# fpga.net
KiCad netlist of a schematic drawn in Altium Designer
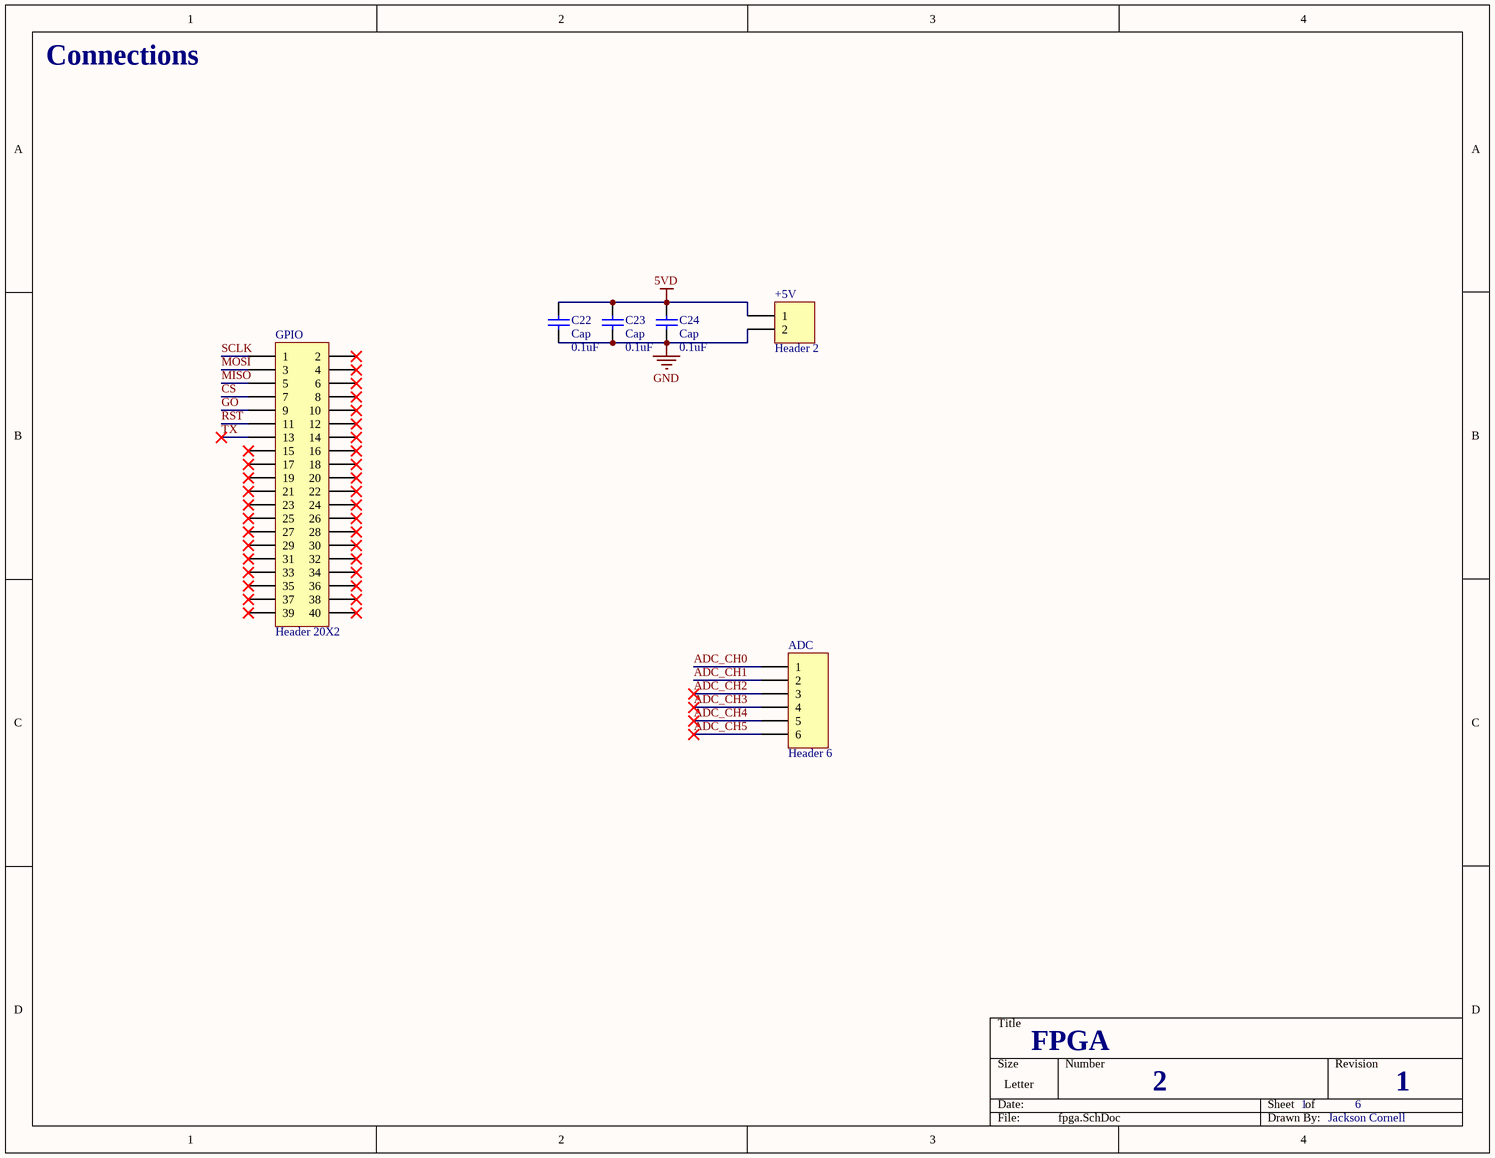
[diagram p0: fpga.SchDoc]

(export (version "E")
  (design (tool "Eeschema 10.0.6"))
  (components
    (comp (ref "+5V")
      (value "Header 2")
      (footprint "HDR1X2")
      (description "Header, 2-Pin")
      (fields (field (name "PUBLISHER") "Altium Limited"))
      (libsource (lib "Miscellaneous Connectors") (part "Header 2"))
    )
    (comp (ref "ADC")
      (value "Header 6")
      (footprint "HDR1X6")
      (description "Header, 6-Pin")
      (fields (field (name "PUBLISHER") "Altium Limited"))
      (libsource (lib "Miscellaneous Connectors") (part "Header 6"))
    )
    (comp (ref "C22")
      (value "Cap")
      (footprint "CAPC0805")
      (description "Capacitor")
      (fields (field (name "ALTIUM_VALUE") "0.1uF") (field (name "PUBLISHER") "Altium Limited"))
      (libsource (lib "Miscellaneous Devices") (part "Cap"))
    )
    (comp (ref "C23")
      (value "Cap")
      (footprint "CAPC0805")
      (description "Capacitor")
      (fields (field (name "ALTIUM_VALUE") "0.1uF") (field (name "PUBLISHER") "Altium Limited"))
      (libsource (lib "Miscellaneous Devices") (part "Cap"))
    )
    (comp (ref "C24")
      (value "Cap")
      (footprint "CAPC0805")
      (description "Capacitor")
      (fields (field (name "ALTIUM_VALUE") "0.1uF") (field (name "PUBLISHER") "Altium Limited"))
      (libsource (lib "Miscellaneous Devices") (part "Cap"))
    )
    (comp (ref "GPIO")
      (value "Header 20X2")
      (footprint "HDR2X20")
      (description "Header, 20-Pin, Dual row")
      (fields (field (name "PUBLISHER") "Altium Limited"))
      (libsource (lib "Miscellaneous Connectors") (part "Header 20X2"))
    )
  )
  (nets
    (net (code "1") (name "/ADC_CH0") (class "Default")
      (node (ref "ADC") (pin "1") (pinfunction "1_1") (pintype "passive"))
    )
    (net (code "2") (name "/ADC_CH1") (class "Default")
      (node (ref "ADC") (pin "2") (pinfunction "2_2") (pintype "passive"))
    )
    (net (code "3") (name "/ADC_CH2") (class "Default")
      (node (ref "ADC") (pin "3") (pinfunction "3_3") (pintype "passive+no_connect"))
    )
    (net (code "4") (name "/ADC_CH3") (class "Default")
      (node (ref "ADC") (pin "4") (pinfunction "4_4") (pintype "passive+no_connect"))
    )
    (net (code "5") (name "/ADC_CH4") (class "Default")
      (node (ref "ADC") (pin "5") (pinfunction "5_5") (pintype "passive+no_connect"))
    )
    (net (code "6") (name "/ADC_CH5") (class "Default")
      (node (ref "ADC") (pin "6") (pinfunction "6_6") (pintype "passive+no_connect"))
    )
    (net (code "7") (name "/CS") (class "Default")
      (node (ref "GPIO") (pin "7") (pinfunction "7_7") (pintype "passive"))
    )
    (net (code "8") (name "/GO") (class "Default")
      (node (ref "GPIO") (pin "9") (pinfunction "9_9") (pintype "passive"))
    )
    (net (code "9") (name "/MISO") (class "Default")
      (node (ref "GPIO") (pin "5") (pinfunction "5_5") (pintype "passive"))
    )
    (net (code "10") (name "/MOSI") (class "Default")
      (node (ref "GPIO") (pin "3") (pinfunction "3_3") (pintype "passive"))
    )
    (net (code "11") (name "/RST") (class "Default")
      (node (ref "GPIO") (pin "11") (pinfunction "11_11") (pintype "passive"))
    )
    (net (code "12") (name "/SCLK") (class "Default")
      (node (ref "GPIO") (pin "1") (pinfunction "1_1") (pintype "passive"))
    )
    (net (code "13") (name "/TX") (class "Default")
      (node (ref "GPIO") (pin "13") (pinfunction "13_13") (pintype "passive+no_connect"))
    )
    (net (code "14") (name "5VD") (class "Default")
      (node (ref "+5V") (pin "1") (pinfunction "1_1") (pintype "passive"))
      (node (ref "C22") (pin "2") (pinfunction "2_2") (pintype "passive"))
      (node (ref "C23") (pin "2") (pinfunction "2_2") (pintype "passive"))
      (node (ref "C24") (pin "2") (pinfunction "2_2") (pintype "passive"))
    )
    (net (code "15") (name "GND") (class "Default")
      (node (ref "+5V") (pin "2") (pinfunction "2_2") (pintype "passive"))
      (node (ref "C22") (pin "1") (pinfunction "1_1") (pintype "passive"))
      (node (ref "C23") (pin "1") (pinfunction "1_1") (pintype "passive"))
      (node (ref "C24") (pin "1") (pinfunction "1_1") (pintype "passive"))
    )
    (net (code "16") (name "unconnected-(GPIO-Pad2)") (class "Default")
      (node (ref "GPIO") (pin "2") (pinfunction "2_2") (pintype "passive+no_connect"))
    )
    (net (code "17") (name "unconnected-(GPIO-Pad4)") (class "Default")
      (node (ref "GPIO") (pin "4") (pinfunction "4_4") (pintype "passive+no_connect"))
    )
    (net (code "18") (name "unconnected-(GPIO-Pad6)") (class "Default")
      (node (ref "GPIO") (pin "6") (pinfunction "6_6") (pintype "passive+no_connect"))
    )
    (net (code "19") (name "unconnected-(GPIO-Pad8)") (class "Default")
      (node (ref "GPIO") (pin "8") (pinfunction "8_8") (pintype "passive+no_connect"))
    )
    (net (code "20") (name "unconnected-(GPIO-Pad10)") (class "Default")
      (node (ref "GPIO") (pin "10") (pinfunction "10_10") (pintype "passive+no_connect"))
    )
    (net (code "21") (name "unconnected-(GPIO-Pad12)") (class "Default")
      (node (ref "GPIO") (pin "12") (pinfunction "12_12") (pintype "passive+no_connect"))
    )
    (net (code "22") (name "unconnected-(GPIO-Pad14)") (class "Default")
      (node (ref "GPIO") (pin "14") (pinfunction "14_14") (pintype "passive+no_connect"))
    )
    (net (code "23") (name "unconnected-(GPIO-Pad15)") (class "Default")
      (node (ref "GPIO") (pin "15") (pinfunction "15_15") (pintype "passive+no_connect"))
    )
    (net (code "24") (name "unconnected-(GPIO-Pad16)") (class "Default")
      (node (ref "GPIO") (pin "16") (pinfunction "16_16") (pintype "passive+no_connect"))
    )
    (net (code "25") (name "unconnected-(GPIO-Pad17)") (class "Default")
      (node (ref "GPIO") (pin "17") (pinfunction "17_17") (pintype "passive+no_connect"))
    )
    (net (code "26") (name "unconnected-(GPIO-Pad18)") (class "Default")
      (node (ref "GPIO") (pin "18") (pinfunction "18_18") (pintype "passive+no_connect"))
    )
    (net (code "27") (name "unconnected-(GPIO-Pad19)") (class "Default")
      (node (ref "GPIO") (pin "19") (pinfunction "19_19") (pintype "passive+no_connect"))
    )
    (net (code "28") (name "unconnected-(GPIO-Pad20)") (class "Default")
      (node (ref "GPIO") (pin "20") (pinfunction "20_20") (pintype "passive+no_connect"))
    )
    (net (code "29") (name "unconnected-(GPIO-Pad21)") (class "Default")
      (node (ref "GPIO") (pin "21") (pinfunction "21_21") (pintype "passive+no_connect"))
    )
    (net (code "30") (name "unconnected-(GPIO-Pad22)") (class "Default")
      (node (ref "GPIO") (pin "22") (pinfunction "22_22") (pintype "passive+no_connect"))
    )
    (net (code "31") (name "unconnected-(GPIO-Pad23)") (class "Default")
      (node (ref "GPIO") (pin "23") (pinfunction "23_23") (pintype "passive+no_connect"))
    )
    (net (code "32") (name "unconnected-(GPIO-Pad24)") (class "Default")
      (node (ref "GPIO") (pin "24") (pinfunction "24_24") (pintype "passive+no_connect"))
    )
    (net (code "33") (name "unconnected-(GPIO-Pad25)") (class "Default")
      (node (ref "GPIO") (pin "25") (pinfunction "25_25") (pintype "passive+no_connect"))
    )
    (net (code "34") (name "unconnected-(GPIO-Pad26)") (class "Default")
      (node (ref "GPIO") (pin "26") (pinfunction "26_26") (pintype "passive+no_connect"))
    )
    (net (code "35") (name "unconnected-(GPIO-Pad27)") (class "Default")
      (node (ref "GPIO") (pin "27") (pinfunction "27_27") (pintype "passive+no_connect"))
    )
    (net (code "36") (name "unconnected-(GPIO-Pad28)") (class "Default")
      (node (ref "GPIO") (pin "28") (pinfunction "28_28") (pintype "passive+no_connect"))
    )
    (net (code "37") (name "unconnected-(GPIO-Pad29)") (class "Default")
      (node (ref "GPIO") (pin "29") (pinfunction "29_29") (pintype "passive+no_connect"))
    )
    (net (code "38") (name "unconnected-(GPIO-Pad30)") (class "Default")
      (node (ref "GPIO") (pin "30") (pinfunction "30_30") (pintype "passive+no_connect"))
    )
    (net (code "39") (name "unconnected-(GPIO-Pad31)") (class "Default")
      (node (ref "GPIO") (pin "31") (pinfunction "31_31") (pintype "passive+no_connect"))
    )
    (net (code "40") (name "unconnected-(GPIO-Pad32)") (class "Default")
      (node (ref "GPIO") (pin "32") (pinfunction "32_32") (pintype "passive+no_connect"))
    )
    (net (code "41") (name "unconnected-(GPIO-Pad33)") (class "Default")
      (node (ref "GPIO") (pin "33") (pinfunction "33_33") (pintype "passive+no_connect"))
    )
    (net (code "42") (name "unconnected-(GPIO-Pad34)") (class "Default")
      (node (ref "GPIO") (pin "34") (pinfunction "34_34") (pintype "passive+no_connect"))
    )
    (net (code "43") (name "unconnected-(GPIO-Pad35)") (class "Default")
      (node (ref "GPIO") (pin "35") (pinfunction "35_35") (pintype "passive+no_connect"))
    )
    (net (code "44") (name "unconnected-(GPIO-Pad36)") (class "Default")
      (node (ref "GPIO") (pin "36") (pinfunction "36_36") (pintype "passive+no_connect"))
    )
    (net (code "45") (name "unconnected-(GPIO-Pad37)") (class "Default")
      (node (ref "GPIO") (pin "37") (pinfunction "37_37") (pintype "passive+no_connect"))
    )
    (net (code "46") (name "unconnected-(GPIO-Pad38)") (class "Default")
      (node (ref "GPIO") (pin "38") (pinfunction "38_38") (pintype "passive+no_connect"))
    )
    (net (code "47") (name "unconnected-(GPIO-Pad39)") (class "Default")
      (node (ref "GPIO") (pin "39") (pinfunction "39_39") (pintype "passive+no_connect"))
    )
    (net (code "48") (name "unconnected-(GPIO-Pad40)") (class "Default")
      (node (ref "GPIO") (pin "40") (pinfunction "40_40") (pintype "passive+no_connect"))
    )
  )
)
